# H_Bridge.net
KiCad netlist of a schematic drawn in Altium Designer
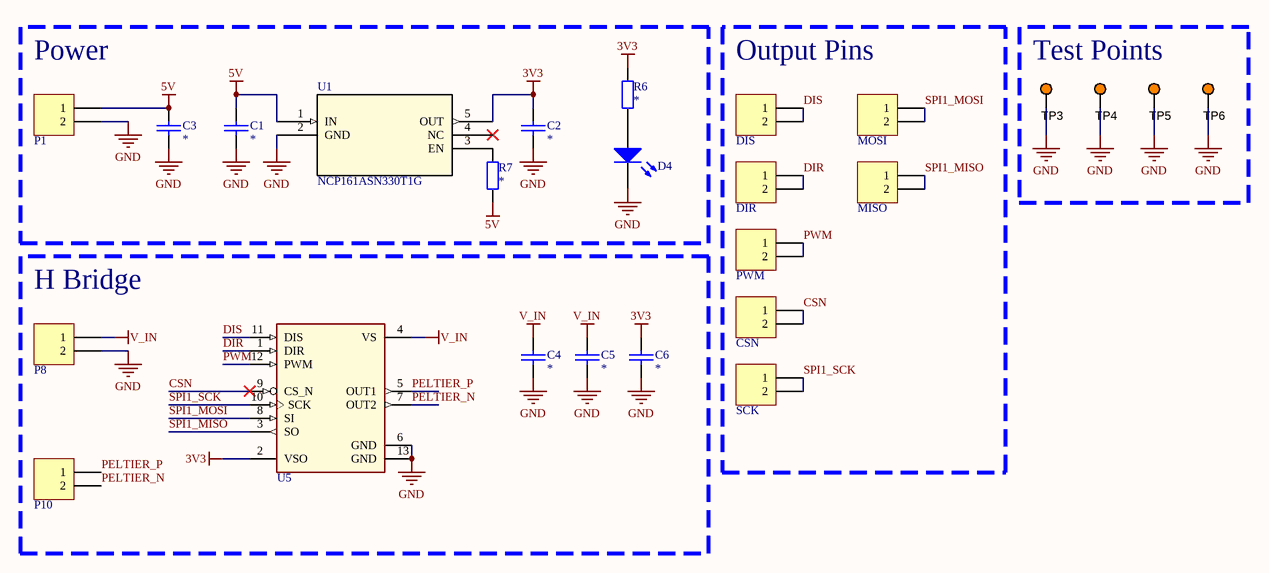
[diagram p0: H_Bridge.SchDoc]

(export (version "E")
  (design (tool "Eeschema 10.0.6"))
  (components
    (comp (ref "C1")
      (value "*")
      (footprint "0805 CAP")
      (description "SMT ceramic capacitor 0805 size")
      (libsource (lib "EE209_SchLib") (part "CerCap_SMT_0805"))
    )
    (comp (ref "C2")
      (value "*")
      (footprint "0805 CAP")
      (description "SMT ceramic capacitor 0805 size")
      (libsource (lib "EE209_SchLib") (part "CerCap_SMT_0805"))
    )
    (comp (ref "C3")
      (value "*")
      (footprint "0805 CAP")
      (description "SMT ceramic capacitor 0805 size")
      (libsource (lib "EE209_SchLib") (part "CerCap_SMT_0805"))
    )
    (comp (ref "C4")
      (value "*")
      (footprint "0805 CAP")
      (description "SMT ceramic capacitor 0805 size")
      (libsource (lib "EE209_SchLib") (part "CerCap_SMT_0805"))
    )
    (comp (ref "C5")
      (value "*")
      (footprint "0805 CAP")
      (description "SMT ceramic capacitor 0805 size")
      (libsource (lib "EE209_SchLib") (part "CerCap_SMT_0805"))
    )
    (comp (ref "C6")
      (value "*")
      (footprint "0805 CAP")
      (description "SMT ceramic capacitor 0805 size")
      (libsource (lib "EE209_SchLib") (part "CerCap_SMT_0805"))
    )
    (comp (ref "CSN")
      (value "2 Way")
      (footprint "ECE-600102STTH")
      (description "HEADER POLARISED 2WAY TH")
      (libsource (lib "EceParts") (part "Header 2"))
    )
    (comp (ref "D4")
      (value "LTST-C170KGKT")
      (footprint "0805 LED")
      (description "SMT LED 0805 size")
      (fields (field (name "MANUFACTURER") "Lite-On Inc."))
      (libsource (lib "EE209_SchLib") (part "LED_SMT_0805"))
    )
    (comp (ref "DIR")
      (value "2 Way")
      (footprint "ECE-600102STTH")
      (description "HEADER POLARISED 2WAY TH")
      (libsource (lib "EceParts") (part "Header 2"))
    )
    (comp (ref "DIS")
      (value "2 Way")
      (footprint "ECE-600102STTH")
      (description "HEADER POLARISED 2WAY TH")
      (libsource (lib "EceParts") (part "Header 2"))
    )
    (comp (ref "MISO")
      (value "2 Way")
      (footprint "ECE-600102STTH")
      (description "HEADER POLARISED 2WAY TH")
      (libsource (lib "EceParts") (part "Header 2"))
    )
    (comp (ref "MOSI")
      (value "2 Way")
      (footprint "ECE-600102STTH")
      (description "HEADER POLARISED 2WAY TH")
      (libsource (lib "EceParts") (part "Header 2"))
    )
    (comp (ref "P1")
      (value "2 Way")
      (footprint "ECE-600102STTH")
      (description "HEADER POLARISED 2WAY TH")
      (libsource (lib "EceParts") (part "Header 2"))
    )
    (comp (ref "P8")
      (value "2 Way")
      (footprint "ECE-600102STTH")
      (description "HEADER POLARISED 2WAY TH")
      (libsource (lib "EceParts") (part "Header 2"))
    )
    (comp (ref "P10")
      (value "2 Way")
      (footprint "ECE-600102STTH")
      (description "HEADER POLARISED 2WAY TH")
      (libsource (lib "EceParts") (part "Header 2"))
    )
    (comp (ref "PWM")
      (value "2 Way")
      (footprint "ECE-600102STTH")
      (description "HEADER POLARISED 2WAY TH")
      (libsource (lib "EceParts") (part "Header 2"))
    )
    (comp (ref "R6")
      (value "*")
      (footprint "0805 RES")
      (description "0805 resistor")
      (fields (field (name "PUBLISHER") "Altium Limited"))
      (libsource (lib "EE209_SchLib") (part "Res_SMT_0805"))
    )
    (comp (ref "R7")
      (value "*")
      (footprint "0805 RES")
      (description "0805 resistor")
      (fields (field (name "PUBLISHER") "Altium Limited"))
      (libsource (lib "EE209_SchLib") (part "Res_SMT_0805"))
    )
    (comp (ref "SCK")
      (value "2 Way")
      (footprint "ECE-600102STTH")
      (description "HEADER POLARISED 2WAY TH")
      (libsource (lib "EceParts") (part "Header 2"))
    )
    (comp (ref "TP3")
      (value "5003")
      (footprint "EE209_PcbLib:TP_TH")
      (description "Test Point, Orange, 1-Pin THD, RoHS")
      (libsource (lib "EE209_SchLib") (part "TestPoint"))
    )
    (comp (ref "TP4")
      (value "5003")
      (footprint "EE209_PcbLib:TP_TH")
      (description "Test Point, Orange, 1-Pin THD, RoHS")
      (libsource (lib "EE209_SchLib") (part "TestPoint"))
    )
    (comp (ref "TP5")
      (value "5003")
      (footprint "EE209_PcbLib:TP_TH")
      (description "Test Point, Orange, 1-Pin THD, RoHS")
      (libsource (lib "EE209_SchLib") (part "TestPoint"))
    )
    (comp (ref "TP6")
      (value "5003")
      (footprint "EE209_PcbLib:TP_TH")
      (description "Test Point, Orange, 1-Pin THD, RoHS")
      (libsource (lib "EE209_SchLib") (part "TestPoint"))
    )
    (comp (ref "U1")
      (value "NCP161ASN330T1G")
      (footprint "SOT23_527AH_ONS")
      (description "Description")
      (fields (field (name "COPYRIGHT") "Copyright (C) 2026 Ultra Librarian. All rights reserved."))
      (libsource (lib "NCP161ASN330T1G") (part "NCP161ASN330T1G"))
    )
    (comp (ref "U5")
      (value "IFX9201SG")
      (footprint "SOP100P1030X260-13N")
      (description "6 A H-Bridge with SPI")
      (fields (field (name "MANUFACTURER") "Infineon Technologies"))
      (libsource (lib "IFX9201SG") (part "IFX9201SG"))
    )
  )
  (nets
    (net (code "1") (name "/CSN") (class "Default")
      (node (ref "CSN") (pin "1") (pinfunction "1_1") (pintype "passive"))
      (node (ref "CSN") (pin "2") (pinfunction "2_2") (pintype "passive"))
      (node (ref "U5") (pin "9") (pinfunction "CS_N_9") (pintype "input"))
    )
    (net (code "2") (name "/DIR") (class "Default")
      (node (ref "DIR") (pin "1") (pinfunction "1_1") (pintype "passive"))
      (node (ref "DIR") (pin "2") (pinfunction "2_2") (pintype "passive"))
      (node (ref "U5") (pin "1") (pinfunction "DIR_1") (pintype "input"))
    )
    (net (code "3") (name "/DIS") (class "Default")
      (node (ref "DIS") (pin "1") (pinfunction "1_1") (pintype "passive"))
      (node (ref "DIS") (pin "2") (pinfunction "2_2") (pintype "passive"))
      (node (ref "U5") (pin "11") (pinfunction "DIS_11") (pintype "input"))
    )
    (net (code "4") (name "/PELTIER_N") (class "Default")
      (node (ref "P10") (pin "2") (pinfunction "2_2") (pintype "passive"))
      (node (ref "U5") (pin "7") (pinfunction "OUT2_7") (pintype "output"))
    )
    (net (code "5") (name "/PELTIER_P") (class "Default")
      (node (ref "P10") (pin "1") (pinfunction "1_1") (pintype "passive"))
      (node (ref "U5") (pin "5") (pinfunction "OUT1_5") (pintype "output"))
    )
    (net (code "6") (name "/PWM") (class "Default")
      (node (ref "PWM") (pin "1") (pinfunction "1_1") (pintype "passive"))
      (node (ref "PWM") (pin "2") (pinfunction "2_2") (pintype "passive"))
      (node (ref "U5") (pin "12") (pinfunction "PWM_12") (pintype "input"))
    )
    (net (code "7") (name "/SPI1_MISO") (class "Default")
      (node (ref "MISO") (pin "1") (pinfunction "1_1") (pintype "passive"))
      (node (ref "MISO") (pin "2") (pinfunction "2_2") (pintype "passive"))
      (node (ref "U5") (pin "3") (pinfunction "SO_3") (pintype "output"))
    )
    (net (code "8") (name "/SPI1_MOSI") (class "Default")
      (node (ref "MOSI") (pin "1") (pinfunction "1_1") (pintype "passive"))
      (node (ref "MOSI") (pin "2") (pinfunction "2_2") (pintype "passive"))
      (node (ref "U5") (pin "8") (pinfunction "SI_8") (pintype "input"))
    )
    (net (code "9") (name "/SPI1_SCK") (class "Default")
      (node (ref "SCK") (pin "1") (pinfunction "1_1") (pintype "passive"))
      (node (ref "SCK") (pin "2") (pinfunction "2_2") (pintype "passive"))
      (node (ref "U5") (pin "10") (pinfunction "SCK_10") (pintype "input"))
    )
    (net (code "10") (name "3V3") (class "Default")
      (node (ref "C2") (pin "1") (pinfunction "1_1") (pintype "passive"))
      (node (ref "C6") (pin "1") (pinfunction "1_1") (pintype "passive"))
      (node (ref "R6") (pin "1") (pinfunction "1_1") (pintype "passive"))
      (node (ref "U1") (pin "5") (pinfunction "OUT_5") (pintype "output"))
      (node (ref "U5") (pin "2") (pinfunction "VSO_2") (pintype "power_in"))
    )
    (net (code "11") (name "5V") (class "Default")
      (node (ref "C1") (pin "1") (pinfunction "1_1") (pintype "passive"))
      (node (ref "C3") (pin "1") (pinfunction "1_1") (pintype "passive"))
      (node (ref "P1") (pin "1") (pinfunction "1_1") (pintype "passive"))
      (node (ref "R7") (pin "2") (pinfunction "2_2") (pintype "passive"))
      (node (ref "U1") (pin "1") (pinfunction "IN_1") (pintype "input"))
    )
    (net (code "12") (name "GND") (class "Default")
      (node (ref "C1") (pin "2") (pinfunction "2_2") (pintype "passive"))
      (node (ref "C2") (pin "2") (pinfunction "2_2") (pintype "passive"))
      (node (ref "C3") (pin "2") (pinfunction "2_2") (pintype "passive"))
      (node (ref "C4") (pin "2") (pinfunction "2_2") (pintype "passive"))
      (node (ref "C5") (pin "2") (pinfunction "2_2") (pintype "passive"))
      (node (ref "C6") (pin "2") (pinfunction "2_2") (pintype "passive"))
      (node (ref "D4") (pin "2") (pinfunction "K_2") (pintype "passive"))
      (node (ref "P1") (pin "2") (pinfunction "2_2") (pintype "passive"))
      (node (ref "P8") (pin "2") (pinfunction "2_2") (pintype "passive"))
      (node (ref "TP3") (pin "1") (pinfunction "1_1") (pintype "passive"))
      (node (ref "TP4") (pin "1") (pinfunction "1_1") (pintype "passive"))
      (node (ref "TP5") (pin "1") (pinfunction "1_1") (pintype "passive"))
      (node (ref "TP6") (pin "1") (pinfunction "1_1") (pintype "passive"))
      (node (ref "U1") (pin "2") (pinfunction "GND_2") (pintype "power_in"))
      (node (ref "U5") (pin "13") (pinfunction "GND_13") (pintype "power_in"))
      (node (ref "U5") (pin "6") (pinfunction "GND_6") (pintype "power_in"))
    )
    (net (code "13") (name "Net-(D4-A)") (class "Default")
      (node (ref "D4") (pin "1") (pinfunction "A_1") (pintype "passive"))
      (node (ref "R6") (pin "2") (pinfunction "2_2") (pintype "passive"))
    )
    (net (code "14") (name "Net-(U1-EN)") (class "Default")
      (node (ref "R7") (pin "1") (pinfunction "1_1") (pintype "passive"))
      (node (ref "U1") (pin "3") (pinfunction "EN_3") (pintype "passive"))
    )
    (net (code "15") (name "V_IN") (class "Default")
      (node (ref "C4") (pin "1") (pinfunction "1_1") (pintype "passive"))
      (node (ref "C5") (pin "1") (pinfunction "1_1") (pintype "passive"))
      (node (ref "P8") (pin "1") (pinfunction "1_1") (pintype "passive"))
      (node (ref "U5") (pin "4") (pinfunction "VS_4") (pintype "power_in"))
    )
    (net (code "16") (name "unconnected-(U1-NC-Pad4)") (class "Default")
      (node (ref "U1") (pin "4") (pinfunction "NC_4") (pintype "passive+no_connect"))
    )
  )
)
